# Elekid_01.net
KiCad netlist of a schematic drawn in Altium Designer
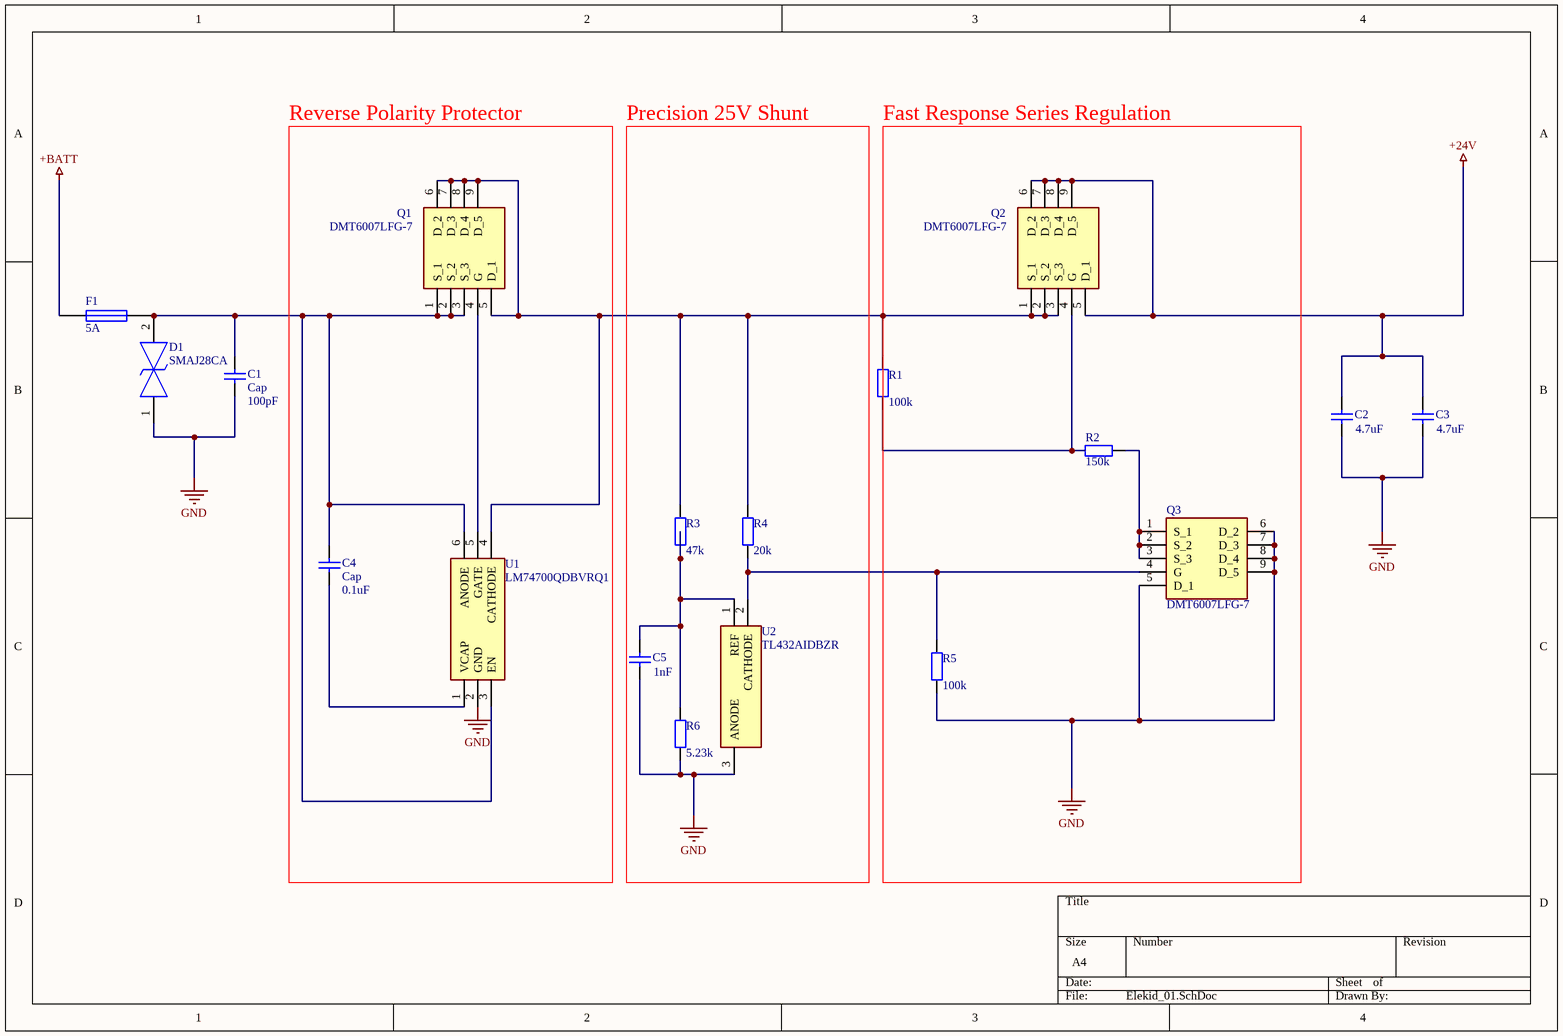
[diagram p0: Elekid_01.SchDoc]

(export (version "E")
  (design (tool "Eeschema 10.0.6"))
  (components
    (comp (ref "C1")
      (value "Cap")
      (footprint "C0805")
      (description "Capacitor")
      (fields (field (name "ALTIUM_VALUE") "100pF") (field (name "PUBLISHER") "Altium Limited"))
      (libsource (lib "Miscellaneous Devices") (part "Cap"))
    )
    (comp (ref "C2")
      (value "4.7uF")
      (footprint "C0805")
      (description "Capacitor")
      (fields (field (name "Comment") "Cap") (field (name "PUBLISHER") "Altium Limited"))
      (libsource (lib "Miscellaneous Devices") (part "Cap"))
    )
    (comp (ref "C3")
      (value "4.7uF")
      (footprint "C0805")
      (description "Capacitor")
      (fields (field (name "Comment") "Cap") (field (name "PUBLISHER") "Altium Limited"))
      (libsource (lib "Miscellaneous Devices") (part "Cap"))
    )
    (comp (ref "C4")
      (value "Cap")
      (footprint "C0805")
      (description "Capacitor")
      (fields (field (name "ALTIUM_VALUE") "0.1uF") (field (name "PUBLISHER") "Altium Limited"))
      (libsource (lib "Miscellaneous Devices") (part "Cap"))
    )
    (comp (ref "C5")
      (value "1nF")
      (footprint "C0805")
      (description "Capacitor")
      (fields (field (name "Comment") "Cap") (field (name "PUBLISHER") "Altium Limited"))
      (libsource (lib "Miscellaneous Devices") (part "Cap"))
    )
    (comp (ref "D1")
      (value "SMAJ28CA")
      (footprint "Embedded:DIONM5226X262N")
      (description "TVS Diode (Bi-directional)")
      (fields (field (name "MOUSER PART NUMBER") "652-SMAJ28CA"))
      (libsource (lib "*") (part "SMAJ28CA"))
    )
    (comp (ref "F1")
      (value "5A")
      (footprint "PIN-W2/E2.8")
      (description "Fuse")
      (fields (field (name "PUBLISHER") "Altium Limited"))
      (libsource (lib "Miscellaneous Devices") (part "Fuse 1"))
    )
    (comp (ref "Q1")
      (value "DMT6007LFG-7")
      (footprint "Embedded:DMT6007LFG7")
      (description "MOSFET (N-Channel)")
      (fields (field (name "MOUSER PART NUMBER") "621-DMT6007LFG-7"))
      (libsource (lib "*") (part "DMT6007LFG-7"))
    )
    (comp (ref "Q2")
      (value "DMT6007LFG-7")
      (footprint "Embedded:DMT6007LFG7")
      (description "MOSFET (N-Channel)")
      (fields (field (name "MOUSER PART NUMBER") "621-DMT6007LFG-7"))
      (libsource (lib "*") (part "DMT6007LFG-7"))
    )
    (comp (ref "Q3")
      (value "DMT6007LFG-7")
      (footprint "Embedded:DMT6007LFG7")
      (description "MOSFET (N-Channel)")
      (fields (field (name "MOUSER PART NUMBER") "621-DMT6007LFG-7"))
      (libsource (lib "") (part "DMT6007LFG-7_1"))
    )
    (comp (ref "R1")
      (value "100k")
      (footprint "C0805")
      (description "Resistor")
      (fields (field (name "Comment") "Res2") (field (name "PUBLISHER") "Altium Limited"))
      (libsource (lib "Miscellaneous Devices") (part "Res2"))
    )
    (comp (ref "R2")
      (value "150k")
      (footprint "C0805")
      (description "Resistor")
      (fields (field (name "Comment") "Res2") (field (name "PUBLISHER") "Altium Limited"))
      (libsource (lib "") (part "Res2_1"))
    )
    (comp (ref "R3")
      (value "47k")
      (footprint "C0805")
      (description "Resistor")
      (fields (field (name "Comment") "Res2") (field (name "PUBLISHER") "Altium Limited"))
      (libsource (lib "Miscellaneous Devices") (part "Res2"))
    )
    (comp (ref "R4")
      (value "20k")
      (footprint "C0805")
      (description "Resistor")
      (fields (field (name "Comment") "Res2") (field (name "PUBLISHER") "Altium Limited"))
      (libsource (lib "Miscellaneous Devices") (part "Res2"))
    )
    (comp (ref "R5")
      (value "100k")
      (footprint "C0805")
      (description "Resistor")
      (fields (field (name "Comment") "Res2") (field (name "PUBLISHER") "Altium Limited"))
      (libsource (lib "Miscellaneous Devices") (part "Res2"))
    )
    (comp (ref "R6")
      (value "5.23k")
      (footprint "C0805")
      (description "Resistor")
      (fields (field (name "Comment") "Res2") (field (name "PUBLISHER") "Altium Limited"))
      (libsource (lib "Miscellaneous Devices") (part "Res2"))
    )
    (comp (ref "U1")
      (value "LM74700QDBVRQ1")
      (footprint "Embedded:SOT95P280X145-6N")
      (description "Integrated Circuit")
      (fields (field (name "MOUSER PART NUMBER") "595-LM74700QDBVRQ1"))
      (libsource (lib "*") (part "LM74700QDBVRQ1"))
    )
    (comp (ref "U2")
      (value "TL432AIDBZR")
      (footprint "Embedded:SOT95P237X112-3N")
      (description "Integrated Circuit")
      (fields (field (name "MOUSER PART NUMBER") "595-TL432AIDBZR"))
      (libsource (lib "*") (part "TL432AIDBZR"))
    )
  )
  (nets
    (net (code "1") (name "+24V") (class "Default")
      (node (ref "C2") (pin "2") (pinfunction "2_2") (pintype "passive"))
      (node (ref "C3") (pin "2") (pinfunction "2_2") (pintype "passive"))
      (node (ref "Q2") (pin "5") (pinfunction "D_1_5") (pintype "passive"))
      (node (ref "Q2") (pin "6") (pinfunction "D_2_6") (pintype "passive"))
      (node (ref "Q2") (pin "7") (pinfunction "D_3_7") (pintype "passive"))
      (node (ref "Q2") (pin "8") (pinfunction "D_4_8") (pintype "passive"))
      (node (ref "Q2") (pin "9") (pinfunction "D_5_9") (pintype "passive"))
    )
    (net (code "2") (name "+BATT") (class "Default")
      (node (ref "F1") (pin "1") (pinfunction "1_1") (pintype "passive"))
    )
    (net (code "3") (name "GND") (class "Default")
      (node (ref "C1") (pin "1") (pinfunction "1_1") (pintype "passive"))
      (node (ref "C2") (pin "1") (pinfunction "1_1") (pintype "passive"))
      (node (ref "C3") (pin "1") (pinfunction "1_1") (pintype "passive"))
      (node (ref "C5") (pin "1") (pinfunction "1_1") (pintype "passive"))
      (node (ref "D1") (pin "1") (pinfunction "1_1") (pintype "passive"))
      (node (ref "Q3") (pin "5") (pinfunction "D_1_5") (pintype "passive"))
      (node (ref "Q3") (pin "6") (pinfunction "D_2_6") (pintype "passive"))
      (node (ref "Q3") (pin "7") (pinfunction "D_3_7") (pintype "passive"))
      (node (ref "Q3") (pin "8") (pinfunction "D_4_8") (pintype "passive"))
      (node (ref "Q3") (pin "9") (pinfunction "D_5_9") (pintype "passive"))
      (node (ref "R5") (pin "1") (pinfunction "1_1") (pintype "passive"))
      (node (ref "R6") (pin "1") (pinfunction "1_1") (pintype "passive"))
      (node (ref "U1") (pin "2") (pinfunction "GND_2") (pintype "passive"))
      (node (ref "U2") (pin "3") (pinfunction "ANODE_3") (pintype "passive"))
    )
    (net (code "4") (name "Net-(Q1-D_1)") (class "Default")
      (node (ref "Q1") (pin "5") (pinfunction "D_1_5") (pintype "passive"))
      (node (ref "Q1") (pin "6") (pinfunction "D_2_6") (pintype "passive"))
      (node (ref "Q1") (pin "7") (pinfunction "D_3_7") (pintype "passive"))
      (node (ref "Q1") (pin "8") (pinfunction "D_4_8") (pintype "passive"))
      (node (ref "Q1") (pin "9") (pinfunction "D_5_9") (pintype "passive"))
      (node (ref "Q2") (pin "1") (pinfunction "S_1_1") (pintype "passive"))
      (node (ref "Q2") (pin "2") (pinfunction "S_2_2") (pintype "passive"))
      (node (ref "Q2") (pin "3") (pinfunction "S_3_3") (pintype "passive"))
      (node (ref "R1") (pin "2") (pinfunction "2_2") (pintype "passive"))
      (node (ref "R3") (pin "2") (pinfunction "2_2") (pintype "passive"))
      (node (ref "R4") (pin "2") (pinfunction "2_2") (pintype "passive"))
      (node (ref "U1") (pin "4") (pinfunction "CATHODE_4") (pintype "passive"))
    )
    (net (code "5") (name "Net-(Q1-G)") (class "Default")
      (node (ref "Q1") (pin "4") (pinfunction "G_4") (pintype "passive"))
      (node (ref "U1") (pin "5") (pinfunction "GATE_5") (pintype "passive"))
    )
    (net (code "6") (name "Net-(Q1-S_1)") (class "Default")
      (node (ref "C1") (pin "2") (pinfunction "2_2") (pintype "passive"))
      (node (ref "C4") (pin "2") (pinfunction "2_2") (pintype "passive"))
      (node (ref "D1") (pin "2") (pinfunction "2_2") (pintype "passive"))
      (node (ref "F1") (pin "2") (pinfunction "2_2") (pintype "passive"))
      (node (ref "Q1") (pin "1") (pinfunction "S_1_1") (pintype "passive"))
      (node (ref "Q1") (pin "2") (pinfunction "S_2_2") (pintype "passive"))
      (node (ref "Q1") (pin "3") (pinfunction "S_3_3") (pintype "passive"))
      (node (ref "U1") (pin "3") (pinfunction "EN_3") (pintype "passive"))
      (node (ref "U1") (pin "6") (pinfunction "ANODE_6") (pintype "passive"))
    )
    (net (code "7") (name "Net-(Q2-G)") (class "Default")
      (node (ref "Q2") (pin "4") (pinfunction "G_4") (pintype "passive"))
      (node (ref "R1") (pin "1") (pinfunction "1_1") (pintype "passive"))
      (node (ref "R2") (pin "2") (pinfunction "2_2") (pintype "passive"))
    )
    (net (code "8") (name "Net-(Q3-G)") (class "Default")
      (node (ref "Q3") (pin "4") (pinfunction "G_4") (pintype "passive"))
      (node (ref "R4") (pin "1") (pinfunction "1_1") (pintype "passive"))
      (node (ref "R5") (pin "2") (pinfunction "2_2") (pintype "passive"))
      (node (ref "U2") (pin "2") (pinfunction "CATHODE_2") (pintype "passive"))
    )
    (net (code "9") (name "Net-(Q3-S_1)") (class "Default")
      (node (ref "Q3") (pin "1") (pinfunction "S_1_1") (pintype "passive"))
      (node (ref "Q3") (pin "2") (pinfunction "S_2_2") (pintype "passive"))
      (node (ref "Q3") (pin "3") (pinfunction "S_3_3") (pintype "passive"))
      (node (ref "R2") (pin "1") (pinfunction "1_1") (pintype "passive"))
    )
    (net (code "10") (name "Net-(U1-VCAP)") (class "Default")
      (node (ref "C4") (pin "1") (pinfunction "1_1") (pintype "passive"))
      (node (ref "U1") (pin "1") (pinfunction "VCAP_1") (pintype "passive"))
    )
    (net (code "11") (name "Net-(U2-REF)") (class "Default")
      (node (ref "C5") (pin "2") (pinfunction "2_2") (pintype "passive"))
      (node (ref "R3") (pin "1") (pinfunction "1_1") (pintype "passive"))
      (node (ref "R6") (pin "2") (pinfunction "2_2") (pintype "passive"))
      (node (ref "U2") (pin "1") (pinfunction "REF_1") (pintype "passive"))
    )
  )
)
